# MCU.net
KiCad netlist of a schematic drawn in Altium Designer
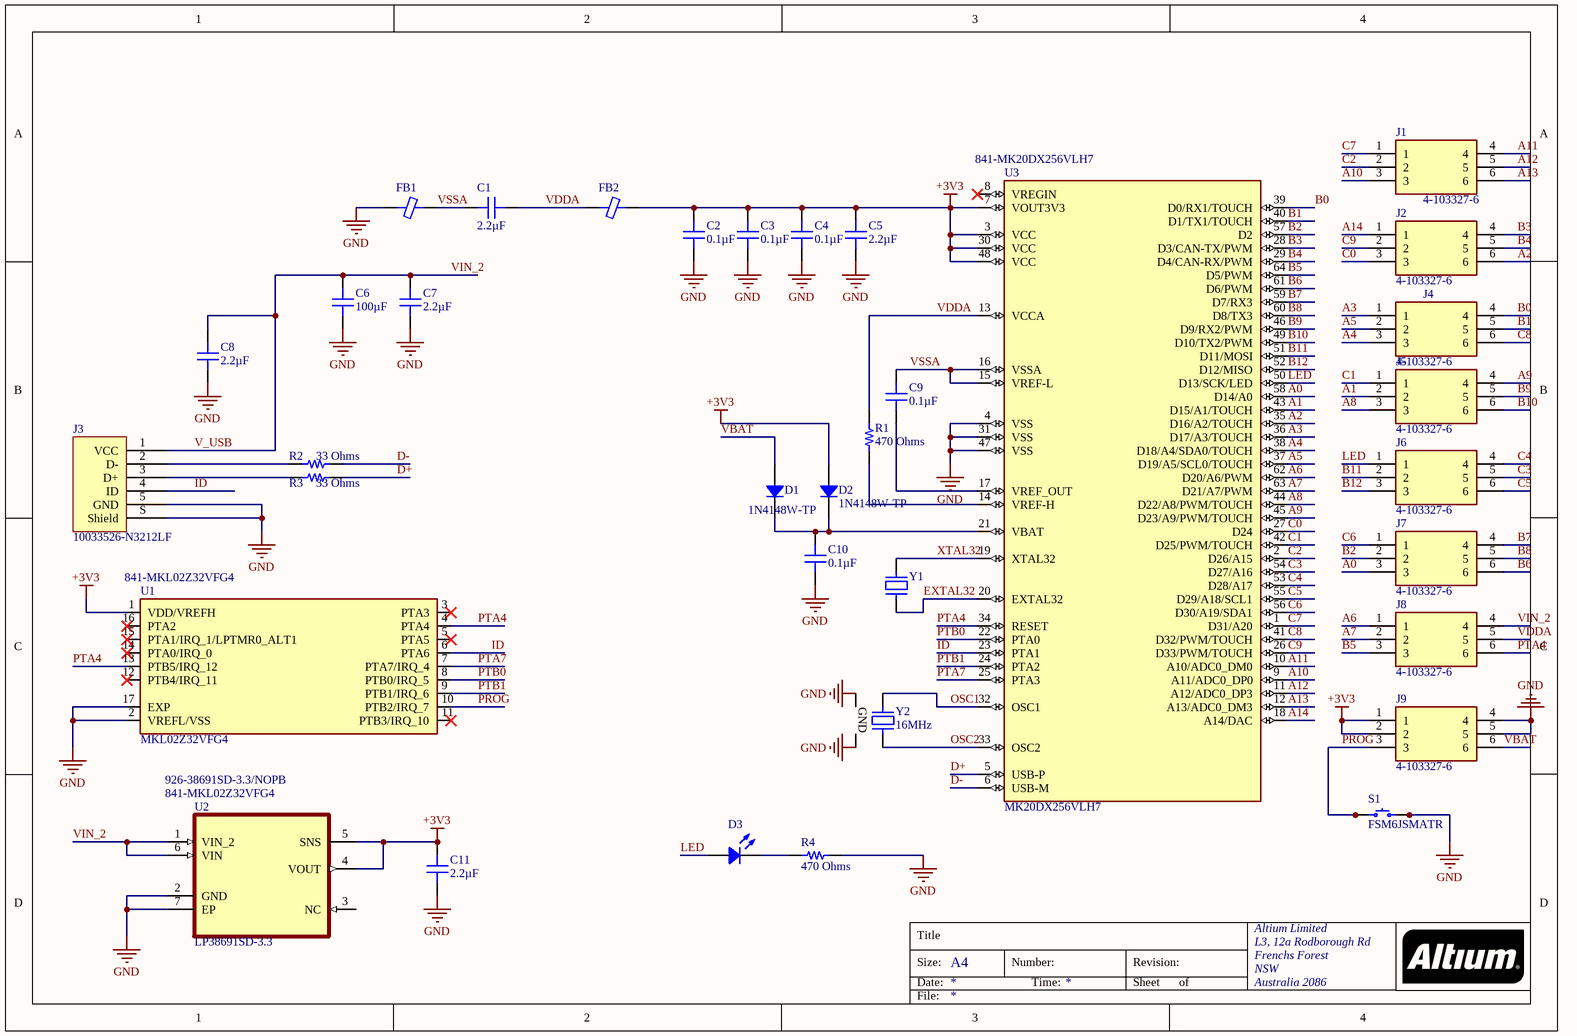
[diagram p0: MCU.SchDoc]

(export (version "E")
  (design (tool "Eeschema 10.0.6"))
  (components
    (comp (ref "C1")
      (value "2.2µF")
      (footprint "CAP 0805_2012")
      (description "CAP CER 2.2UF 50V X7R 0805")
      (fields
        (field (name "PART NUMBER") "CGA4J3X7R1H225K125AB")
        (field (name "MANUFACTURER") "TDK Corporation")
      )
      (libsource (lib "Celestial Altium Library - altium_library") (part "Capacitor"))
    )
    (comp (ref "C2")
      (value "0.1µF")
      (footprint "CAP 0805_2012")
      (description "CAP CER 0805 0.1UF 100V X7R")
      (fields (field (name "PART NUMBER") "C0805C104K1RECAUTO") (field (name "MANUFACTURER") "KEMET"))
      (libsource (lib "Celestial Altium Library - altium_library") (part "Capacitor"))
    )
    (comp (ref "C3")
      (value "0.1µF")
      (footprint "CAP 0805_2012")
      (description "CAP CER 0805 0.1UF 100V X7R")
      (fields (field (name "PART NUMBER") "C0805C104K1RECAUTO") (field (name "MANUFACTURER") "KEMET"))
      (libsource (lib "Celestial Altium Library - altium_library") (part "Capacitor"))
    )
    (comp (ref "C4")
      (value "0.1µF")
      (footprint "CAP 0805_2012")
      (description "CAP CER 0805 0.1UF 100V X7R")
      (fields (field (name "PART NUMBER") "C0805C104K1RECAUTO") (field (name "MANUFACTURER") "KEMET"))
      (libsource (lib "Celestial Altium Library - altium_library") (part "Capacitor"))
    )
    (comp (ref "C5")
      (value "2.2µF")
      (footprint "CAP 0805_2012")
      (description "CAP CER 2.2UF 50V X7R 0805")
      (fields
        (field (name "PART NUMBER") "CGA4J3X7R1H225K125AB")
        (field (name "MANUFACTURER") "TDK Corporation")
      )
      (libsource (lib "Celestial Altium Library - altium_library") (part "Capacitor"))
    )
    (comp (ref "C6")
      (value "100µF")
      (footprint "CAP 0805_2012")
      (description "CAP CER 100UF 6.3V X5R 0805")
      (fields
        (field (name "PART NUMBER") "GRM21BR60J107ME15L")
        (field (name "MANUFACTURER") "Murata Electronics")
      )
      (libsource (lib "Celestial Altium Library - altium_library") (part "Capacitor"))
    )
    (comp (ref "C7")
      (value "2.2µF")
      (footprint "CAP 0805_2012")
      (description "CAP CER 2.2UF 50V X7R 0805")
      (fields
        (field (name "PART NUMBER") "CGA4J3X7R1H225K125AB")
        (field (name "MANUFACTURER") "TDK Corporation")
      )
      (libsource (lib "Celestial Altium Library - altium_library") (part "Capacitor"))
    )
    (comp (ref "C8")
      (value "2.2µF")
      (footprint "CAP 0805_2012")
      (description "CAP CER 2.2UF 50V X7R 0805")
      (fields
        (field (name "PART NUMBER") "CGA4J3X7R1H225K125AB")
        (field (name "MANUFACTURER") "TDK Corporation")
      )
      (libsource (lib "Celestial Altium Library - altium_library") (part "Capacitor"))
    )
    (comp (ref "C9")
      (value "0.1µF")
      (footprint "CAP 0805_2012")
      (description "CAP CER 0805 0.1UF 100V X7R")
      (fields (field (name "PART NUMBER") "C0805C104K1RECAUTO") (field (name "MANUFACTURER") "KEMET"))
      (libsource (lib "Celestial Altium Library - altium_library") (part "Capacitor"))
    )
    (comp (ref "C10")
      (value "0.1µF")
      (footprint "CAP 0805_2012")
      (description "CAP CER 0805 0.1UF 100V X7R")
      (fields (field (name "PART NUMBER") "C0805C104K1RECAUTO") (field (name "MANUFACTURER") "KEMET"))
      (libsource (lib "Celestial Altium Library - altium_library") (part "Capacitor"))
    )
    (comp (ref "C11")
      (value "2.2µF")
      (footprint "CAP 0805_2012")
      (description "CAP CER 2.2UF 50V X7R 0805")
      (fields
        (field (name "PART NUMBER") "CGA4J3X7R1H225K125AB")
        (field (name "MANUFACTURER") "TDK Corporation")
      )
      (libsource (lib "Celestial Altium Library - altium_library") (part "Capacitor"))
    )
    (comp (ref "D1")
      (value "1N4148W-TP")
      (footprint "SOD-123")
      (description "DIODE GEN PURP 100V 150MA SOD123")
      (fields (field (name "MANUFACTURER") "Micro Commercial Co"))
      (libsource (lib "Celestial Altium Library - altium_library") (part "Diode"))
    )
    (comp (ref "D2")
      (value "1N4148W-TP")
      (footprint "SOD-123")
      (description "DIODE GEN PURP 100V 150MA SOD123")
      (fields (field (name "MANUFACTURER") "Micro Commercial Co"))
      (libsource (lib "Celestial Altium Library - altium_library") (part "Diode"))
    )
    (comp (ref "D3")
      (value "JE2835AWT-00-0000-000A0HG830E")
      (footprint "CREE J 2835")
      (description "CREE J SERIES JE2835 LIGHT EMITT")
      (fields (field (name "MANUFACTURER") "Cree Inc."))
      (libsource (lib "Celestial Altium Library - altium_library") (part "LED"))
    )
    (comp (ref "FB1")
      (value "600 Ohms @ 100MHz")
      (footprint "FER 0805_2012")
      (description "FERRITE BEAD 600 OHM 0805 1LN")
      (fields (field (name "PART NUMBER") "MPZ2012S601AT000") (field (name "MANUFACTURER") "TDK Corporation"))
      (libsource (lib "Celestial Altium Library - altium_library") (part "Ferrite Chip"))
    )
    (comp (ref "FB2")
      (value "600 Ohms @ 100MHz")
      (footprint "FER 0805_2012")
      (description "FERRITE BEAD 600 OHM 0805 1LN")
      (fields (field (name "PART NUMBER") "MPZ2012S601AT000") (field (name "MANUFACTURER") "TDK Corporation"))
      (libsource (lib "Celestial Altium Library - altium_library") (part "Ferrite Chip"))
    )
    (comp (ref "J1")
      (value "4-103327-6")
      (footprint "TE_4-103327-6")
      (description "6 Position Single Row 2.54 mm Through-Hole Straight AMPMODU Breakaway Header")
      (fields (field (name "MF") "TE Connectivity"))
      (libsource (lib "4-103327-6") (part "4-103327-6"))
    )
    (comp (ref "J2")
      (value "4-103327-6")
      (footprint "TE_4-103327-6")
      (description "6 Position Single Row 2.54 mm Through-Hole Straight AMPMODU Breakaway Header")
      (fields (field (name "MF") "TE Connectivity"))
      (libsource (lib "4-103327-6") (part "4-103327-6"))
    )
    (comp (ref "J3")
      (value "10033526-N3212LF")
      (footprint "FCI USB 10033526-N3212LF")
      (description "CONN RCPT MINI USB B 5POS SMD RA")
      (fields (field (name "MANUFACTURER") "Amphenol ICC (FCI)"))
      (libsource (lib "Celestial Altium Library - altium_library") (part "USB 2.0 Type B Micro"))
    )
    (comp (ref "J4")
      (value "4-103327-6")
      (footprint "TE_4-103327-6")
      (description "6 Position Single Row 2.54 mm Through-Hole Straight AMPMODU Breakaway Header")
      (fields (field (name "MF") "TE Connectivity"))
      (libsource (lib "4-103327-6") (part "4-103327-6"))
    )
    (comp (ref "J5")
      (value "4-103327-6")
      (footprint "TE_4-103327-6")
      (description "6 Position Single Row 2.54 mm Through-Hole Straight AMPMODU Breakaway Header")
      (fields (field (name "MF") "TE Connectivity"))
      (libsource (lib "4-103327-6") (part "4-103327-6"))
    )
    (comp (ref "J6")
      (value "4-103327-6")
      (footprint "TE_4-103327-6")
      (description "6 Position Single Row 2.54 mm Through-Hole Straight AMPMODU Breakaway Header")
      (fields (field (name "MF") "TE Connectivity"))
      (libsource (lib "4-103327-6") (part "4-103327-6"))
    )
    (comp (ref "J7")
      (value "4-103327-6")
      (footprint "TE_4-103327-6")
      (description "6 Position Single Row 2.54 mm Through-Hole Straight AMPMODU Breakaway Header")
      (fields (field (name "MF") "TE Connectivity"))
      (libsource (lib "4-103327-6") (part "4-103327-6"))
    )
    (comp (ref "J8")
      (value "4-103327-6")
      (footprint "TE_4-103327-6")
      (description "6 Position Single Row 2.54 mm Through-Hole Straight AMPMODU Breakaway Header")
      (fields (field (name "MF") "TE Connectivity"))
      (libsource (lib "4-103327-6") (part "4-103327-6"))
    )
    (comp (ref "J9")
      (value "4-103327-6")
      (footprint "TE_4-103327-6")
      (description "6 Position Single Row 2.54 mm Through-Hole Straight AMPMODU Breakaway Header")
      (fields (field (name "MF") "TE Connectivity"))
      (libsource (lib "4-103327-6") (part "4-103327-6"))
    )
    (comp (ref "R1")
      (value "470 Ohms")
      (footprint "RES 0805_2012")
      (description "RES SMD 470 OHM 0.1% 1/10W 0805")
      (fields
        (field (name "PART NUMBER") "CPF0805B470RE1")
        (field (name "MANUFACTURER") "TE Connectivity Passive Product")
      )
      (libsource (lib "Celestial Altium Library - altium_library") (part "Resistor"))
    )
    (comp (ref "R2")
      (value "33 Ohms")
      (footprint "RES 0805_2012")
      (description "RES SMD 33 OHM 0.1% 1/10W 0805")
      (fields
        (field (name "PART NUMBER") "CPF0805B33RE1")
        (field (name "MANUFACTURER") "TE Connectivity Passive Product")
      )
      (libsource (lib "Celestial Altium Library - altium_library") (part "Resistor"))
    )
    (comp (ref "R3")
      (value "33 Ohms")
      (footprint "RES 0805_2012")
      (description "RES SMD 33 OHM 0.1% 1/10W 0805")
      (fields
        (field (name "PART NUMBER") "CPF0805B33RE1")
        (field (name "MANUFACTURER") "TE Connectivity Passive Product")
      )
      (libsource (lib "Celestial Altium Library - altium_library") (part "Resistor"))
    )
    (comp (ref "R4")
      (value "470 Ohms")
      (footprint "RES 0805_2012")
      (description "RES 470 OHM 1% 1/8W 0805")
      (fields
        (field (name "PART NUMBER") "RMCF0805FT470R")
        (field (name "MANUFACTURER") "Stackpole Electronics Inc")
      )
      (libsource (lib "Celestial Altium Library - altium_library") (part "Resistor"))
    )
    (comp (ref "S1")
      (value "FSM6JSMATR")
      (footprint "TE FSM6JSMA")
      (description "SWITCH TACTILE SPST-NO 0.05A 24V")
      (fields (field (name "MANUFACTURER") "TE Connectivity ALCOSWITCH Switches"))
      (libsource (lib "Celestial Altium Library - altium_library") (part "SPST-NO 4 PIN"))
    )
    (comp (ref "U1")
      (value "MKL02Z32VFG4")
      (footprint "QFN50P300X300X65-17N")
      (description "IC MCU 32BIT 32KB FLASH 16QFN")
      (fields
        (field (name "MF") "NXP USA")
        (field (name "SUPPLIER PART NUMBER 1") "841-MKL02Z32VFG4")
        (field (name "MANUFACTURER") "NXP Freescale")
      )
      (libsource (lib "MKL02Z32VFG4") (part "MKL02Z32VFG4"))
    )
    (comp (ref "U2")
      (value "LP38691SD-3.3")
      (footprint "DFN300X300X80-7N")
      (description "IC REG LINEAR 3.3V 500MA 6WSON")
      (fields
        (field (name "MF") "Texas Instruments")
        (field (name "SUPPLIER PART NUMBER 1") "841-MKL02Z32VFG4")
        (field (name "SUPPLIER PART NUMBER 2") "926-38691SD-3.3/NOPB")
        (field (name "MANUFACTURER") "TI National Semiconductor")
      )
      (libsource (lib "LP38691SD-3.3") (part "LP38691SD-3.3"))
    )
    (comp (ref "U3")
      (value "MK20DX256VLH7")
      (footprint "QFP50P1200X1200X160-64N")
      (fields
        (field (name "MF") "NXP USA")
        (field (name "SUPPLIER PART NUMBER 1") "841-MK20DX256VLH7")
        (field (name "MANUFACTURER") "NXP Freescale")
      )
      (libsource (lib "MK20DX256VLH7") (part "MK20DX256VLH7"))
    )
    (comp (ref "Y1")
      (value "32.768kHz")
      (footprint "ABRACON ABS06")
      (description "CRYSTAL 32.7680KHZ 12.5PF SMD")
      (fields (field (name "PART NUMBER") "ABS06-32.768KHZ-1-T") (field (name "MANUFACTURER") "Abracon LLC"))
      (libsource (lib "Celestial Altium Library - altium_library") (part "Abracon Crystal ABS06"))
    )
    (comp (ref "Y2")
      (value "16MHz")
      (footprint "NDK NX3225SA")
      (description "CRYSTAL 16.0000MHZ 8PF SMD")
      (fields
        (field (name "PART NUMBER") "NX3225SA-16.000M-STD-CSR-1")
        (field (name "MANUFACTURER") "NDK America, Inc.")
      )
      (libsource (lib "Celestial Altium Library - altium_library") (part "NDK Crystal NX3225SA"))
    )
  )
  (nets
    (net (code "1") (name "+3V3") (class "Default")
      (node (ref "C11") (pin "2") (pinfunction "2_2") (pintype "passive"))
      (node (ref "C2") (pin "2") (pinfunction "2_2") (pintype "passive"))
      (node (ref "C3") (pin "2") (pinfunction "2_2") (pintype "passive"))
      (node (ref "C4") (pin "2") (pinfunction "2_2") (pintype "passive"))
      (node (ref "C5") (pin "2") (pinfunction "2_2") (pintype "passive"))
      (node (ref "D2") (pin "1") (pinfunction "1_1") (pintype "passive"))
      (node (ref "FB2") (pin "1") (pinfunction "1_1") (pintype "passive"))
      (node (ref "J9") (pin "1") (pinfunction "1_1") (pintype "passive"))
      (node (ref "J9") (pin "2") (pinfunction "2_2") (pintype "passive"))
      (node (ref "U1") (pin "1") (pinfunction "VDD/VREFH_1") (pintype "power_in"))
      (node (ref "U2") (pin "4") (pinfunction "VOUT_4") (pintype "output"))
      (node (ref "U2") (pin "5") (pinfunction "SNS_5") (pintype "passive"))
      (node (ref "U3") (pin "3") (pinfunction "VCC_3") (pintype "bidirectional"))
      (node (ref "U3") (pin "30") (pinfunction "VCC_30") (pintype "bidirectional"))
      (node (ref "U3") (pin "48") (pinfunction "VCC_48") (pintype "bidirectional"))
      (node (ref "U3") (pin "7") (pinfunction "VOUT3V3_7") (pintype "bidirectional"))
    )
    (net (code "2") (name "/A0") (class "Default")
      (node (ref "J7") (pin "3") (pinfunction "3_3") (pintype "passive"))
      (node (ref "U3") (pin "58") (pinfunction "D14/A0_58") (pintype "bidirectional"))
    )
    (net (code "3") (name "/A1") (class "Default")
      (node (ref "J5") (pin "2") (pinfunction "2_2") (pintype "passive"))
      (node (ref "U3") (pin "43") (pinfunction "D15/A1/TOUCH_43") (pintype "bidirectional"))
    )
    (net (code "4") (name "/A2") (class "Default")
      (node (ref "J2") (pin "6") (pinfunction "6_6") (pintype "passive"))
      (node (ref "U3") (pin "35") (pinfunction "D16/A2/TOUCH_35") (pintype "bidirectional"))
    )
    (net (code "5") (name "/A3") (class "Default")
      (node (ref "J4") (pin "1") (pinfunction "1_1") (pintype "passive"))
      (node (ref "U3") (pin "36") (pinfunction "D17/A3/TOUCH_36") (pintype "bidirectional"))
    )
    (net (code "6") (name "/A4") (class "Default")
      (node (ref "J4") (pin "3") (pinfunction "3_3") (pintype "passive"))
      (node (ref "U3") (pin "38") (pinfunction "D18/A4/SDA0/TOUCH_38") (pintype "bidirectional"))
    )
    (net (code "7") (name "/A5") (class "Default")
      (node (ref "J4") (pin "2") (pinfunction "2_2") (pintype "passive"))
      (node (ref "U3") (pin "37") (pinfunction "D19/A5/SCL0/TOUCH_37") (pintype "bidirectional"))
    )
    (net (code "8") (name "/A6") (class "Default")
      (node (ref "J8") (pin "1") (pinfunction "1_1") (pintype "passive"))
      (node (ref "U3") (pin "62") (pinfunction "D20/A6/PWM_62") (pintype "bidirectional"))
    )
    (net (code "9") (name "/A7") (class "Default")
      (node (ref "J8") (pin "2") (pinfunction "2_2") (pintype "passive"))
      (node (ref "U3") (pin "63") (pinfunction "D21/A7/PWM_63") (pintype "bidirectional"))
    )
    (net (code "10") (name "/A8") (class "Default")
      (node (ref "J5") (pin "3") (pinfunction "3_3") (pintype "passive"))
      (node (ref "U3") (pin "44") (pinfunction "D22/A8/PWM/TOUCH_44") (pintype "bidirectional"))
    )
    (net (code "11") (name "/A9") (class "Default")
      (node (ref "J5") (pin "4") (pinfunction "4_4") (pintype "passive"))
      (node (ref "U3") (pin "45") (pinfunction "D23/A9/PWM/TOUCH_45") (pintype "bidirectional"))
    )
    (net (code "12") (name "/A10") (class "Default")
      (node (ref "J1") (pin "3") (pinfunction "3_3") (pintype "passive"))
      (node (ref "U3") (pin "9") (pinfunction "A11/ADC0_DP0_9") (pintype "bidirectional"))
    )
    (net (code "13") (name "/A11") (class "Default")
      (node (ref "J1") (pin "4") (pinfunction "4_4") (pintype "passive"))
      (node (ref "U3") (pin "10") (pinfunction "A10/ADC0_DM0_10") (pintype "bidirectional"))
    )
    (net (code "14") (name "/A12") (class "Default")
      (node (ref "J1") (pin "5") (pinfunction "5_5") (pintype "passive"))
      (node (ref "U3") (pin "11") (pinfunction "A12/ADC0_DP3_11") (pintype "bidirectional"))
    )
    (net (code "15") (name "/A13") (class "Default")
      (node (ref "J1") (pin "6") (pinfunction "6_6") (pintype "passive"))
      (node (ref "U3") (pin "12") (pinfunction "A13/ADC0_DM3_12") (pintype "bidirectional"))
    )
    (net (code "16") (name "/A14") (class "Default")
      (node (ref "J2") (pin "1") (pinfunction "1_1") (pintype "passive"))
      (node (ref "U3") (pin "18") (pinfunction "A14/DAC_18") (pintype "bidirectional"))
    )
    (net (code "17") (name "/B0") (class "Default")
      (node (ref "J4") (pin "4") (pinfunction "4_4") (pintype "passive"))
      (node (ref "U3") (pin "39") (pinfunction "D0/RX1/TOUCH_39") (pintype "bidirectional"))
    )
    (net (code "18") (name "/B1") (class "Default")
      (node (ref "J4") (pin "5") (pinfunction "5_5") (pintype "passive"))
      (node (ref "U3") (pin "40") (pinfunction "D1/TX1/TOUCH_40") (pintype "bidirectional"))
    )
    (net (code "19") (name "/B2") (class "Default")
      (node (ref "J7") (pin "2") (pinfunction "2_2") (pintype "passive"))
      (node (ref "U3") (pin "57") (pinfunction "D2_57") (pintype "bidirectional"))
    )
    (net (code "20") (name "/B3") (class "Default")
      (node (ref "J2") (pin "4") (pinfunction "4_4") (pintype "passive"))
      (node (ref "U3") (pin "28") (pinfunction "D3/CAN-TX/PWM_28") (pintype "bidirectional"))
    )
    (net (code "21") (name "/B4") (class "Default")
      (node (ref "J2") (pin "5") (pinfunction "5_5") (pintype "passive"))
      (node (ref "U3") (pin "29") (pinfunction "D4/CAN-RX/PWM_29") (pintype "bidirectional"))
    )
    (net (code "22") (name "/B5") (class "Default")
      (node (ref "J8") (pin "3") (pinfunction "3_3") (pintype "passive"))
      (node (ref "U3") (pin "64") (pinfunction "D5/PWM_64") (pintype "bidirectional"))
    )
    (net (code "23") (name "/B6") (class "Default")
      (node (ref "J7") (pin "6") (pinfunction "6_6") (pintype "passive"))
      (node (ref "U3") (pin "61") (pinfunction "D6/PWM_61") (pintype "bidirectional"))
    )
    (net (code "24") (name "/B7") (class "Default")
      (node (ref "J7") (pin "4") (pinfunction "4_4") (pintype "passive"))
      (node (ref "U3") (pin "59") (pinfunction "D7/RX3_59") (pintype "bidirectional"))
    )
    (net (code "25") (name "/B8") (class "Default")
      (node (ref "J7") (pin "5") (pinfunction "5_5") (pintype "passive"))
      (node (ref "U3") (pin "60") (pinfunction "D8/TX3_60") (pintype "bidirectional"))
    )
    (net (code "26") (name "/B9") (class "Default")
      (node (ref "J5") (pin "5") (pinfunction "5_5") (pintype "passive"))
      (node (ref "U3") (pin "46") (pinfunction "D9/RX2/PWM_46") (pintype "bidirectional"))
    )
    (net (code "27") (name "/B10") (class "Default")
      (node (ref "J5") (pin "6") (pinfunction "6_6") (pintype "passive"))
      (node (ref "U3") (pin "49") (pinfunction "D10/TX2/PWM_49") (pintype "bidirectional"))
    )
    (net (code "28") (name "/B11") (class "Default")
      (node (ref "J6") (pin "2") (pinfunction "2_2") (pintype "passive"))
      (node (ref "U3") (pin "51") (pinfunction "D11/MOSI_51") (pintype "bidirectional"))
    )
    (net (code "29") (name "/B12") (class "Default")
      (node (ref "J6") (pin "3") (pinfunction "3_3") (pintype "passive"))
      (node (ref "U3") (pin "52") (pinfunction "D12/MISO_52") (pintype "bidirectional"))
    )
    (net (code "30") (name "/C0") (class "Default")
      (node (ref "J2") (pin "3") (pinfunction "3_3") (pintype "passive"))
      (node (ref "U3") (pin "27") (pinfunction "D24_27") (pintype "bidirectional"))
    )
    (net (code "31") (name "/C1") (class "Default")
      (node (ref "J5") (pin "1") (pinfunction "1_1") (pintype "passive"))
      (node (ref "U3") (pin "42") (pinfunction "D25/PWM/TOUCH_42") (pintype "bidirectional"))
    )
    (net (code "32") (name "/C2") (class "Default")
      (node (ref "J1") (pin "2") (pinfunction "2_2") (pintype "passive"))
      (node (ref "U3") (pin "2") (pinfunction "D26/A15_2") (pintype "bidirectional"))
    )
    (net (code "33") (name "/C3") (class "Default")
      (node (ref "J6") (pin "5") (pinfunction "5_5") (pintype "passive"))
      (node (ref "U3") (pin "54") (pinfunction "D27/A16_54") (pintype "bidirectional"))
    )
    (net (code "34") (name "/C4") (class "Default")
      (node (ref "J6") (pin "4") (pinfunction "4_4") (pintype "passive"))
      (node (ref "U3") (pin "53") (pinfunction "D28/A17_53") (pintype "bidirectional"))
    )
    (net (code "35") (name "/C5") (class "Default")
      (node (ref "J6") (pin "6") (pinfunction "6_6") (pintype "passive"))
      (node (ref "U3") (pin "55") (pinfunction "D29/A18/SCL1_55") (pintype "bidirectional"))
    )
    (net (code "36") (name "/C6") (class "Default")
      (node (ref "J7") (pin "1") (pinfunction "1_1") (pintype "passive"))
      (node (ref "U3") (pin "56") (pinfunction "D30/A19/SDA1_56") (pintype "bidirectional"))
    )
    (net (code "37") (name "/C7") (class "Default")
      (node (ref "J1") (pin "1") (pinfunction "1_1") (pintype "passive"))
      (node (ref "U3") (pin "1") (pinfunction "D31/A20_1") (pintype "bidirectional"))
    )
    (net (code "38") (name "/C8") (class "Default")
      (node (ref "J4") (pin "6") (pinfunction "6_6") (pintype "passive"))
      (node (ref "U3") (pin "41") (pinfunction "D32/PWM/TOUCH_41") (pintype "bidirectional"))
    )
    (net (code "39") (name "/C9") (class "Default")
      (node (ref "J2") (pin "2") (pinfunction "2_2") (pintype "passive"))
      (node (ref "U3") (pin "26") (pinfunction "D33/PWM/TOUCH_26") (pintype "bidirectional"))
    )
    (net (code "40") (name "/D+") (class "Default")
      (node (ref "R3") (pin "2") (pinfunction "2_2") (pintype "passive"))
      (node (ref "U3") (pin "5") (pinfunction "USB-P_5") (pintype "bidirectional"))
    )
    (net (code "41") (name "/D-") (class "Default")
      (node (ref "R2") (pin "2") (pinfunction "2_2") (pintype "passive"))
      (node (ref "U3") (pin "6") (pinfunction "USB-M_6") (pintype "bidirectional"))
    )
    (net (code "42") (name "/EXTAL32") (class "Default")
      (node (ref "U3") (pin "20") (pinfunction "EXTAL32_20") (pintype "bidirectional"))
      (node (ref "Y1") (pin "1") (pinfunction "1_1") (pintype "passive"))
    )
    (net (code "43") (name "/ID") (class "Default")
      (node (ref "J3") (pin "4") (pinfunction "ID_4") (pintype "passive"))
      (node (ref "U1") (pin "6") (pinfunction "PTA6_6") (pintype "bidirectional"))
      (node (ref "U3") (pin "23") (pinfunction "PTA1_23") (pintype "bidirectional"))
    )
    (net (code "44") (name "/LED") (class "Default")
      (node (ref "D3") (pin "1") (pinfunction "1_1") (pintype "passive"))
      (node (ref "J6") (pin "1") (pinfunction "1_1") (pintype "passive"))
      (node (ref "U3") (pin "50") (pinfunction "D13/SCK/LED_50") (pintype "bidirectional"))
    )
    (net (code "45") (name "/OSC1") (class "Default")
      (node (ref "U3") (pin "32") (pinfunction "OSC1_32") (pintype "bidirectional"))
      (node (ref "Y2") (pin "1") (pinfunction "1_1") (pintype "passive"))
    )
    (net (code "46") (name "/OSC2") (class "Default")
      (node (ref "U3") (pin "33") (pinfunction "OSC2_33") (pintype "bidirectional"))
      (node (ref "Y2") (pin "3") (pinfunction "3_3") (pintype "passive"))
    )
    (net (code "47") (name "/PROG") (class "Default")
      (node (ref "J9") (pin "3") (pinfunction "3_3") (pintype "passive"))
      (node (ref "S1") (pin "1") (pinfunction "1_1") (pintype "passive"))
      (node (ref "S1") (pin "2") (pinfunction "2_2") (pintype "passive"))
      (node (ref "U1") (pin "10") (pinfunction "PTB2/IRQ_7_10") (pintype "bidirectional"))
    )
    (net (code "48") (name "/PTA4") (class "Default")
      (node (ref "J8") (pin "6") (pinfunction "6_6") (pintype "passive"))
      (node (ref "U1") (pin "13") (pinfunction "PTB5/IRQ_12_13") (pintype "bidirectional"))
      (node (ref "U1") (pin "4") (pinfunction "PTA4_4") (pintype "bidirectional"))
      (node (ref "U3") (pin "34") (pinfunction "RESET_34") (pintype "bidirectional"))
    )
    (net (code "49") (name "/PTA7") (class "Default")
      (node (ref "U1") (pin "7") (pinfunction "PTA7/IRQ_4_7") (pintype "bidirectional"))
      (node (ref "U3") (pin "25") (pinfunction "PTA3_25") (pintype "bidirectional"))
    )
    (net (code "50") (name "/PTB0") (class "Default")
      (node (ref "U1") (pin "8") (pinfunction "PTB0/IRQ_5_8") (pintype "bidirectional"))
      (node (ref "U3") (pin "22") (pinfunction "PTA0_22") (pintype "bidirectional"))
    )
    (net (code "51") (name "/PTB1") (class "Default")
      (node (ref "U1") (pin "9") (pinfunction "PTB1/IRQ_6_9") (pintype "bidirectional"))
      (node (ref "U3") (pin "24") (pinfunction "PTA2_24") (pintype "bidirectional"))
    )
    (net (code "52") (name "/VBAT") (class "Default")
      (node (ref "D1") (pin "1") (pinfunction "1_1") (pintype "passive"))
      (node (ref "J9") (pin "6") (pinfunction "6_6") (pintype "passive"))
    )
    (net (code "53") (name "/VDDA") (class "Default")
      (node (ref "C1") (pin "1") (pinfunction "1_1") (pintype "passive"))
      (node (ref "FB2") (pin "2") (pinfunction "2_2") (pintype "passive"))
      (node (ref "J8") (pin "5") (pinfunction "5_5") (pintype "passive"))
      (node (ref "R1") (pin "2") (pinfunction "2_2") (pintype "passive"))
      (node (ref "U3") (pin "13") (pinfunction "VCCA_13") (pintype "bidirectional"))
    )
    (net (code "54") (name "/VIN_2") (class "Default")
      (node (ref "C6") (pin "2") (pinfunction "2_2") (pintype "passive"))
      (node (ref "C7") (pin "2") (pinfunction "2_2") (pintype "passive"))
      (node (ref "C8") (pin "2") (pinfunction "2_2") (pintype "passive"))
      (node (ref "J3") (pin "1") (pinfunction "VCC_1") (pintype "passive"))
      (node (ref "J8") (pin "4") (pinfunction "4_4") (pintype "passive"))
      (node (ref "U2") (pin "1") (pinfunction "VIN_2_1") (pintype "input"))
      (node (ref "U2") (pin "6") (pinfunction "VIN_6") (pintype "input"))
    )
    (net (code "55") (name "/VSSA") (class "Default")
      (node (ref "C1") (pin "2") (pinfunction "2_2") (pintype "passive"))
      (node (ref "C9") (pin "2") (pinfunction "2_2") (pintype "passive"))
      (node (ref "FB1") (pin "1") (pinfunction "1_1") (pintype "passive"))
      (node (ref "U3") (pin "15") (pinfunction "VREF-L_15") (pintype "bidirectional"))
      (node (ref "U3") (pin "16") (pinfunction "VSSA_16") (pintype "bidirectional"))
    )
    (net (code "56") (name "/XTAL32") (class "Default")
      (node (ref "U3") (pin "19") (pinfunction "XTAL32_19") (pintype "bidirectional"))
      (node (ref "Y1") (pin "2") (pinfunction "2_2") (pintype "passive"))
    )
    (net (code "57") (name "GND") (class "Default")
      (node (ref "C10") (pin "1") (pinfunction "1_1") (pintype "passive"))
      (node (ref "C11") (pin "1") (pinfunction "1_1") (pintype "passive"))
      (node (ref "C2") (pin "1") (pinfunction "1_1") (pintype "passive"))
      (node (ref "C3") (pin "1") (pinfunction "1_1") (pintype "passive"))
      (node (ref "C4") (pin "1") (pinfunction "1_1") (pintype "passive"))
      (node (ref "C5") (pin "1") (pinfunction "1_1") (pintype "passive"))
      (node (ref "C6") (pin "1") (pinfunction "1_1") (pintype "passive"))
      (node (ref "C7") (pin "1") (pinfunction "1_1") (pintype "passive"))
      (node (ref "C8") (pin "1") (pinfunction "1_1") (pintype "passive"))
      (node (ref "FB1") (pin "2") (pinfunction "2_2") (pintype "passive"))
      (node (ref "J3") (pin "5") (pinfunction "GND_5") (pintype "passive"))
      (node (ref "J3") (pin "S") (pinfunction "Shield_S") (pintype "passive"))
      (node (ref "J9") (pin "4") (pinfunction "4_4") (pintype "passive"))
      (node (ref "J9") (pin "5") (pinfunction "5_5") (pintype "passive"))
      (node (ref "R4") (pin "2") (pinfunction "2_2") (pintype "passive"))
      (node (ref "S1") (pin "3") (pinfunction "3_3") (pintype "passive"))
      (node (ref "S1") (pin "4") (pinfunction "4_4") (pintype "passive"))
      (node (ref "U1") (pin "17") (pinfunction "EXP_17") (pintype "power_in"))
      (node (ref "U1") (pin "2") (pinfunction "VREFL/VSS_2") (pintype "power_in"))
      (node (ref "U2") (pin "2") (pinfunction "GND_2") (pintype "passive"))
      (node (ref "U2") (pin "7") (pinfunction "EP_7") (pintype "passive"))
      (node (ref "U3") (pin "31") (pinfunction "VSS_31") (pintype "bidirectional"))
      (node (ref "U3") (pin "4") (pinfunction "VSS_4") (pintype "bidirectional"))
      (node (ref "U3") (pin "47") (pinfunction "VSS_47") (pintype "bidirectional"))
      (node (ref "Y2") (pin "2") (pinfunction "GND_2") (pintype "passive"))
      (node (ref "Y2") (pin "4") (pinfunction "GND_4") (pintype "passive"))
    )
    (net (code "58") (name "Net-(D3-Pad2)") (class "Default")
      (node (ref "D3") (pin "2") (pinfunction "2_2") (pintype "passive"))
      (node (ref "R4") (pin "1") (pinfunction "1_1") (pintype "passive"))
    )
    (net (code "59") (name "Net-(J3-D+)") (class "Default")
      (node (ref "J3") (pin "3") (pinfunction "D+_3") (pintype "passive"))
      (node (ref "R3") (pin "1") (pinfunction "1_1") (pintype "passive"))
    )
    (net (code "60") (name "Net-(J3-D-)") (class "Default")
      (node (ref "J3") (pin "2") (pinfunction "D-_2") (pintype "passive"))
      (node (ref "R2") (pin "1") (pinfunction "1_1") (pintype "passive"))
    )
    (net (code "61") (name "Net-(U3-VBAT)") (class "Default")
      (node (ref "C10") (pin "2") (pinfunction "2_2") (pintype "passive"))
      (node (ref "D1") (pin "2") (pinfunction "2_2") (pintype "passive"))
      (node (ref "D2") (pin "2") (pinfunction "2_2") (pintype "passive"))
      (node (ref "U3") (pin "21") (pinfunction "VBAT_21") (pintype "bidirectional"))
    )
    (net (code "62") (name "Net-(U3-VREF-H)") (class "Default")
      (node (ref "R1") (pin "1") (pinfunction "1_1") (pintype "passive"))
      (node (ref "U3") (pin "14") (pinfunction "VREF-H_14") (pintype "bidirectional"))
    )
    (net (code "63") (name "Net-(U3-VREF_OUT)") (class "Default")
      (node (ref "C9") (pin "1") (pinfunction "1_1") (pintype "passive"))
      (node (ref "U3") (pin "17") (pinfunction "VREF_OUT_17") (pintype "bidirectional"))
    )
    (net (code "64") (name "unconnected-(U1-PTA0{slash}IRQ_0-Pad14)") (class "Default")
      (node (ref "U1") (pin "14") (pinfunction "PTA0/IRQ_0_14") (pintype "bidirectional+no_connect"))
    )
    (net (code "65") (name "unconnected-(U1-PTA1{slash}IRQ_1{slash}LPTMR0_ALT1-Pad15)") (class "Default")
      (node (ref "U1") (pin "15") (pinfunction "PTA1/IRQ_1/LPTMR0_ALT1_15") (pintype "bidirectional+no_connect"))
    )
    (net (code "66") (name "unconnected-(U1-PTA2-Pad16)") (class "Default")
      (node (ref "U1") (pin "16") (pinfunction "PTA2_16") (pintype "bidirectional+no_connect"))
    )
    (net (code "67") (name "unconnected-(U1-PTA3-Pad3)") (class "Default")
      (node (ref "U1") (pin "3") (pinfunction "PTA3_3") (pintype "bidirectional+no_connect"))
    )
    (net (code "68") (name "unconnected-(U1-PTA5-Pad5)") (class "Default")
      (node (ref "U1") (pin "5") (pinfunction "PTA5_5") (pintype "bidirectional+no_connect"))
    )
    (net (code "69") (name "unconnected-(U1-PTB3{slash}IRQ_10-Pad11)") (class "Default")
      (node (ref "U1") (pin "11") (pinfunction "PTB3/IRQ_10_11") (pintype "bidirectional+no_connect"))
    )
    (net (code "70") (name "unconnected-(U1-PTB4{slash}IRQ_11-Pad12)") (class "Default")
      (node (ref "U1") (pin "12") (pinfunction "PTB4/IRQ_11_12") (pintype "bidirectional+no_connect"))
    )
    (net (code "71") (name "unconnected-(U2-NC-Pad3)") (class "Default")
      (node (ref "U2") (pin "3") (pinfunction "NC_3") (pintype "input"))
    )
    (net (code "72") (name "unconnected-(U3-VREGIN-Pad8)") (class "Default")
      (node (ref "U3") (pin "8") (pinfunction "VREGIN_8") (pintype "bidirectional+no_connect"))
    )
  )
)
